# hv_psu_v100_LINREG.net
KiCad netlist of a schematic drawn in Altium Designer
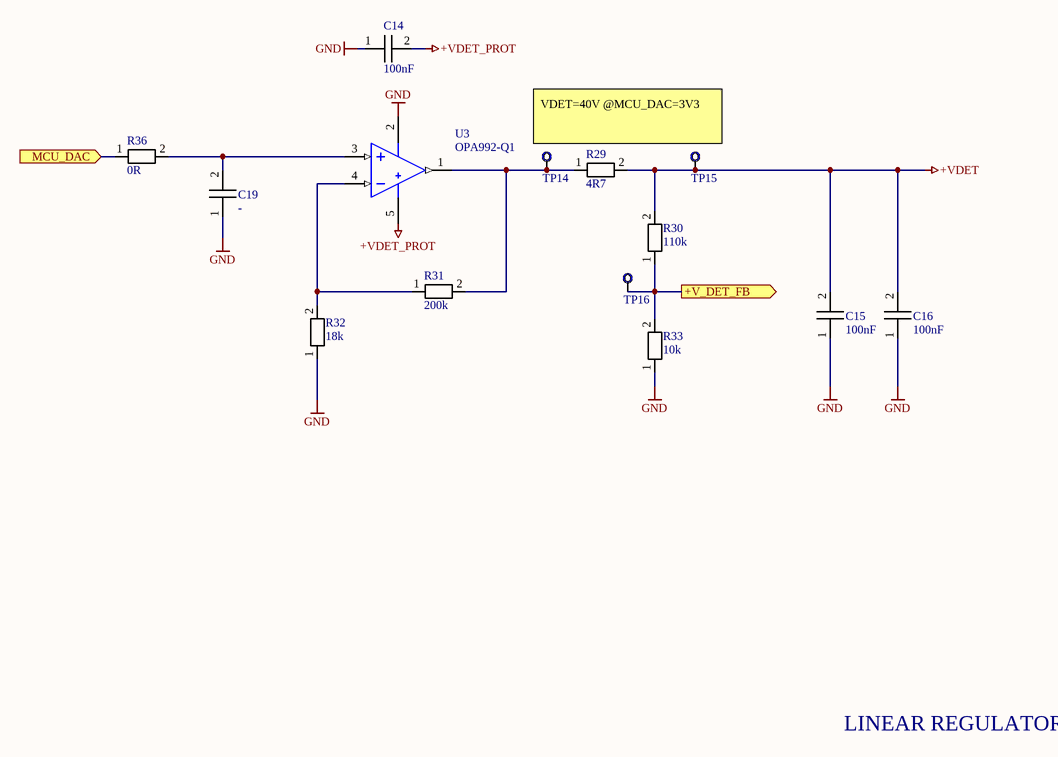
[diagram p0: hv_psu_v100_LINREG.SchDoc]

(export (version "E")
  (design (tool "Eeschema 10.0.6"))
  (components
    (comp (ref "C14") (value "100nF") (footprint "1206_C") (libsource (lib "Schlib1") (part "CAPACITOR")))
    (comp (ref "C15") (value "100nF") (footprint "1206_C") (libsource (lib "Schlib1") (part "CAPACITOR")))
    (comp (ref "C16") (value "100nF") (footprint "1206_C") (libsource (lib "Schlib1") (part "CAPACITOR")))
    (comp (ref "C19") (value "-") (footprint "1206_C") (libsource (lib "Schlib1") (part "CAPACITOR")))
    (comp (ref "R29") (value "4R7") (footprint "1206") (libsource (lib "Schlib1") (part "RESISTOR")))
    (comp (ref "R30") (value "110k") (footprint "1206") (libsource (lib "Schlib1") (part "RESISTOR")))
    (comp (ref "R31") (value "200k") (footprint "1206") (libsource (lib "Schlib1") (part "RESISTOR")))
    (comp (ref "R32") (value "18k") (footprint "1206") (libsource (lib "Schlib1") (part "RESISTOR")))
    (comp (ref "R33") (value "10k") (footprint "1206") (libsource (lib "Schlib1") (part "RESISTOR")))
    (comp (ref "R36") (value "0R") (footprint "1206") (libsource (lib "Schlib1") (part "RESISTOR")))
    (comp (ref "TP14") (value "?") (footprint "PAD_40") (libsource (lib "Schlib1") (part "TESTPOINT")))
    (comp (ref "TP15") (value "?") (footprint "PAD_40") (libsource (lib "Schlib1") (part "TESTPOINT")))
    (comp (ref "TP16") (value "?") (footprint "PAD_40") (libsource (lib "Schlib1") (part "TESTPOINT")))
    (comp (ref "U3")
      (value "OPA992-Q1")
      (footprint "SOT23-5")
      (fields
        (field (name "MOUSER PART NUMBER") "595-INA180A2IDBVR")
        (field (name "MANUFACTURER_PART_NUMBER") "INA180A2IDBVR")
      )
      (libsource (lib "ic_modules") (part "OPA992-Q1"))
    )
  )
  (nets
    (net (code "1") (name "+VDET") (class "Default")
      (node (ref "C15") (pin "2") (pinfunction "2_2") (pintype "passive"))
      (node (ref "C16") (pin "2") (pinfunction "2_2") (pintype "passive"))
      (node (ref "R29") (pin "2") (pinfunction "1_2") (pintype "passive"))
      (node (ref "R30") (pin "2") (pinfunction "1_2") (pintype "passive"))
      (node (ref "TP15") (pin "1") (pinfunction "1_1") (pintype "passive"))
    )
    (net (code "2") (name "+VDET_PROT") (class "Default")
      (node (ref "C14") (pin "2") (pinfunction "2_2") (pintype "passive"))
      (node (ref "U3") (pin "5") (pinfunction "V+_5") (pintype "power_in"))
    )
    (net (code "3") (name "/+V_DET_FB") (class "Default")
      (node (ref "R30") (pin "1") (pinfunction "0_1") (pintype "passive"))
      (node (ref "R33") (pin "2") (pinfunction "1_2") (pintype "passive"))
      (node (ref "TP16") (pin "1") (pinfunction "1_1") (pintype "passive"))
    )
    (net (code "4") (name "/MCU_DAC") (class "Default")
      (node (ref "R36") (pin "1") (pinfunction "0_1") (pintype "passive"))
    )
    (net (code "5") (name "GND") (class "Default")
      (node (ref "C14") (pin "1") (pinfunction "1_1") (pintype "passive"))
      (node (ref "C15") (pin "1") (pinfunction "1_1") (pintype "passive"))
      (node (ref "C16") (pin "1") (pinfunction "1_1") (pintype "passive"))
      (node (ref "C19") (pin "1") (pinfunction "1_1") (pintype "passive"))
      (node (ref "R32") (pin "1") (pinfunction "0_1") (pintype "passive"))
      (node (ref "R33") (pin "1") (pinfunction "0_1") (pintype "passive"))
      (node (ref "U3") (pin "2") (pinfunction "V-_2") (pintype "power_in"))
    )
    (net (code "6") (name "Net-(R29-0)") (class "Default")
      (node (ref "R29") (pin "1") (pinfunction "0_1") (pintype "passive"))
      (node (ref "R31") (pin "2") (pinfunction "1_2") (pintype "passive"))
      (node (ref "TP14") (pin "1") (pinfunction "1_1") (pintype "passive"))
      (node (ref "U3") (pin "1") (pinfunction "OUT_1") (pintype "output"))
    )
    (net (code "7") (name "Net-(R31-0)") (class "Default")
      (node (ref "R31") (pin "1") (pinfunction "0_1") (pintype "passive"))
      (node (ref "R32") (pin "2") (pinfunction "1_2") (pintype "passive"))
      (node (ref "U3") (pin "4") (pinfunction "IN-_4") (pintype "input"))
    )
    (net (code "8") (name "Net-(R36-1)") (class "Default")
      (node (ref "C19") (pin "2") (pinfunction "2_2") (pintype "passive"))
      (node (ref "R36") (pin "2") (pinfunction "1_2") (pintype "passive"))
      (node (ref "U3") (pin "3") (pinfunction "IN+_3") (pintype "input"))
    )
  )
)
